# Sheet1.net
KiCad netlist of a schematic drawn in Altium Designer
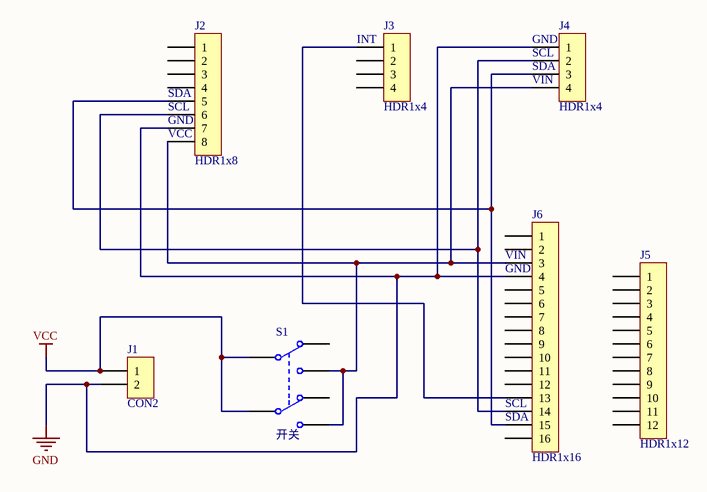
[diagram p0: Sheet1.SchDoc]

(export (version "E")
  (design (tool "Eeschema 10.0.6"))
  (components
    (comp (ref "J1")
      (value "CON2")
      (footprint "HDR1X2")
      (description "Connector")
      (libsource (lib "插件") (part "CON2"))
    )
    (comp (ref "J2")
      (value "HDR1x8")
      (footprint "PIN-8-2.54-1.0")
      (description "Connector")
      (libsource (lib "General") (part "HDR1x8"))
    )
    (comp (ref "J3")
      (value "HDR1x4")
      (footprint "PIN-4-2.54-1.0")
      (description "Connector")
      (libsource (lib "General") (part "HDR1x4"))
    )
    (comp (ref "J4")
      (value "HDR1x4")
      (footprint "PIN-4-2.54-1.0")
      (description "Connector")
      (libsource (lib "General") (part "HDR1x4"))
    )
    (comp (ref "J5")
      (value "HDR1x12")
      (footprint "PIN-12-2.54-1.0")
      (description "Connector")
      (libsource (lib "General") (part "HDR1x12"))
    )
    (comp (ref "J6")
      (value "HDR1x16")
      (footprint "PIN-16-2.54-1.0")
      (description "Connector")
      (libsource (lib "General") (part "HDR1x16"))
    )
    (comp (ref "S1") (value "开关") (footprint "六角开关小") (libsource (lib "开关_按键原理图库") (part "六脚开关")))
  )
  (nets
    (net (code "1") (name "GND") (class "Default")
      (node (ref "J1") (pin "2") (pinfunction "2_2") (pintype "passive"))
      (node (ref "J2") (pin "7") (pinfunction "7_7") (pintype "passive"))
      (node (ref "J4") (pin "1") (pinfunction "1_1") (pintype "passive"))
      (node (ref "J6") (pin "4") (pinfunction "4_4") (pintype "passive"))
    )
    (net (code "2") (name "Net-(J2-Pad5)") (class "Default")
      (node (ref "J2") (pin "5") (pinfunction "5_5") (pintype "passive"))
      (node (ref "J4") (pin "3") (pinfunction "3_3") (pintype "passive"))
      (node (ref "J6") (pin "15") (pinfunction "15_15") (pintype "passive"))
    )
    (net (code "3") (name "Net-(J2-Pad6)") (class "Default")
      (node (ref "J2") (pin "6") (pinfunction "6_6") (pintype "passive"))
      (node (ref "J4") (pin "2") (pinfunction "2_2") (pintype "passive"))
      (node (ref "J6") (pin "14") (pinfunction "14_14") (pintype "passive"))
    )
    (net (code "4") (name "Net-(J3-Pad1)") (class "Default")
      (node (ref "J3") (pin "1") (pinfunction "1_1") (pintype "passive"))
      (node (ref "J6") (pin "13") (pinfunction "13_13") (pintype "passive"))
    )
    (net (code "5") (name "Net-(S1-NO1)") (class "Default")
      (node (ref "J2") (pin "8") (pinfunction "8_8") (pintype "passive"))
      (node (ref "J4") (pin "4") (pinfunction "4_4") (pintype "passive"))
      (node (ref "J6") (pin "3") (pinfunction "3_3") (pintype "passive"))
      (node (ref "S1") (pin "3") (pinfunction "NO1_3") (pintype "passive"))
      (node (ref "S1") (pin "6") (pinfunction "NO2_6") (pintype "passive"))
    )
    (net (code "6") (name "VCC") (class "Default")
      (node (ref "J1") (pin "1") (pinfunction "1_1") (pintype "passive"))
      (node (ref "S1") (pin "1") (pinfunction "COMMON1_1") (pintype "passive"))
      (node (ref "S1") (pin "5") (pinfunction "COMMON2_5") (pintype "passive"))
    )
    (net (code "7") (name "unconnected-(J2-Pad1)") (class "Default")
      (node (ref "J2") (pin "1") (pinfunction "1_1") (pintype "passive"))
    )
    (net (code "8") (name "unconnected-(J2-Pad2)") (class "Default")
      (node (ref "J2") (pin "2") (pinfunction "2_2") (pintype "passive"))
    )
    (net (code "9") (name "unconnected-(J2-Pad3)") (class "Default")
      (node (ref "J2") (pin "3") (pinfunction "3_3") (pintype "passive"))
    )
    (net (code "10") (name "unconnected-(J2-Pad4)") (class "Default")
      (node (ref "J2") (pin "4") (pinfunction "4_4") (pintype "passive"))
    )
    (net (code "11") (name "unconnected-(J3-Pad2)") (class "Default")
      (node (ref "J3") (pin "2") (pinfunction "2_2") (pintype "passive"))
    )
    (net (code "12") (name "unconnected-(J3-Pad3)") (class "Default")
      (node (ref "J3") (pin "3") (pinfunction "3_3") (pintype "passive"))
    )
    (net (code "13") (name "unconnected-(J3-Pad4)") (class "Default")
      (node (ref "J3") (pin "4") (pinfunction "4_4") (pintype "passive"))
    )
    (net (code "14") (name "unconnected-(J5-Pad1)") (class "Default")
      (node (ref "J5") (pin "1") (pinfunction "1_1") (pintype "passive"))
    )
    (net (code "15") (name "unconnected-(J5-Pad2)") (class "Default")
      (node (ref "J5") (pin "2") (pinfunction "2_2") (pintype "passive"))
    )
    (net (code "16") (name "unconnected-(J5-Pad3)") (class "Default")
      (node (ref "J5") (pin "3") (pinfunction "3_3") (pintype "passive"))
    )
    (net (code "17") (name "unconnected-(J5-Pad4)") (class "Default")
      (node (ref "J5") (pin "4") (pinfunction "4_4") (pintype "passive"))
    )
    (net (code "18") (name "unconnected-(J5-Pad5)") (class "Default")
      (node (ref "J5") (pin "5") (pinfunction "5_5") (pintype "passive"))
    )
    (net (code "19") (name "unconnected-(J5-Pad6)") (class "Default")
      (node (ref "J5") (pin "6") (pinfunction "6_6") (pintype "passive"))
    )
    (net (code "20") (name "unconnected-(J5-Pad7)") (class "Default")
      (node (ref "J5") (pin "7") (pinfunction "7_7") (pintype "passive"))
    )
    (net (code "21") (name "unconnected-(J5-Pad8)") (class "Default")
      (node (ref "J5") (pin "8") (pinfunction "8_8") (pintype "passive"))
    )
    (net (code "22") (name "unconnected-(J5-Pad9)") (class "Default")
      (node (ref "J5") (pin "9") (pinfunction "9_9") (pintype "passive"))
    )
    (net (code "23") (name "unconnected-(J5-Pad10)") (class "Default")
      (node (ref "J5") (pin "10") (pinfunction "10_10") (pintype "passive"))
    )
    (net (code "24") (name "unconnected-(J5-Pad11)") (class "Default")
      (node (ref "J5") (pin "11") (pinfunction "11_11") (pintype "passive"))
    )
    (net (code "25") (name "unconnected-(J5-Pad12)") (class "Default")
      (node (ref "J5") (pin "12") (pinfunction "12_12") (pintype "passive"))
    )
    (net (code "26") (name "unconnected-(J6-Pad1)") (class "Default")
      (node (ref "J6") (pin "1") (pinfunction "1_1") (pintype "passive"))
    )
    (net (code "27") (name "unconnected-(J6-Pad2)") (class "Default")
      (node (ref "J6") (pin "2") (pinfunction "2_2") (pintype "passive"))
    )
    (net (code "28") (name "unconnected-(J6-Pad5)") (class "Default")
      (node (ref "J6") (pin "5") (pinfunction "5_5") (pintype "passive"))
    )
    (net (code "29") (name "unconnected-(J6-Pad6)") (class "Default")
      (node (ref "J6") (pin "6") (pinfunction "6_6") (pintype "passive"))
    )
    (net (code "30") (name "unconnected-(J6-Pad7)") (class "Default")
      (node (ref "J6") (pin "7") (pinfunction "7_7") (pintype "passive"))
    )
    (net (code "31") (name "unconnected-(J6-Pad8)") (class "Default")
      (node (ref "J6") (pin "8") (pinfunction "8_8") (pintype "passive"))
    )
    (net (code "32") (name "unconnected-(J6-Pad9)") (class "Default")
      (node (ref "J6") (pin "9") (pinfunction "9_9") (pintype "passive"))
    )
    (net (code "33") (name "unconnected-(J6-Pad10)") (class "Default")
      (node (ref "J6") (pin "10") (pinfunction "10_10") (pintype "passive"))
    )
    (net (code "34") (name "unconnected-(J6-Pad11)") (class "Default")
      (node (ref "J6") (pin "11") (pinfunction "11_11") (pintype "passive"))
    )
    (net (code "35") (name "unconnected-(J6-Pad12)") (class "Default")
      (node (ref "J6") (pin "12") (pinfunction "12_12") (pintype "passive"))
    )
    (net (code "36") (name "unconnected-(J6-Pad16)") (class "Default")
      (node (ref "J6") (pin "16") (pinfunction "16_16") (pintype "passive"))
    )
    (net (code "37") (name "unconnected-(S1-NC1-Pad2)") (class "Default")
      (node (ref "S1") (pin "2") (pinfunction "NC1_2") (pintype "passive"))
    )
    (net (code "38") (name "unconnected-(S1-NC2-Pad4)") (class "Default")
      (node (ref "S1") (pin "4") (pinfunction "NC2_4") (pintype "passive"))
    )
  )
)
